# SCH_Party-Lights_2024-05-11.net
KiCad netlist of a schematic drawn in EasyEDA
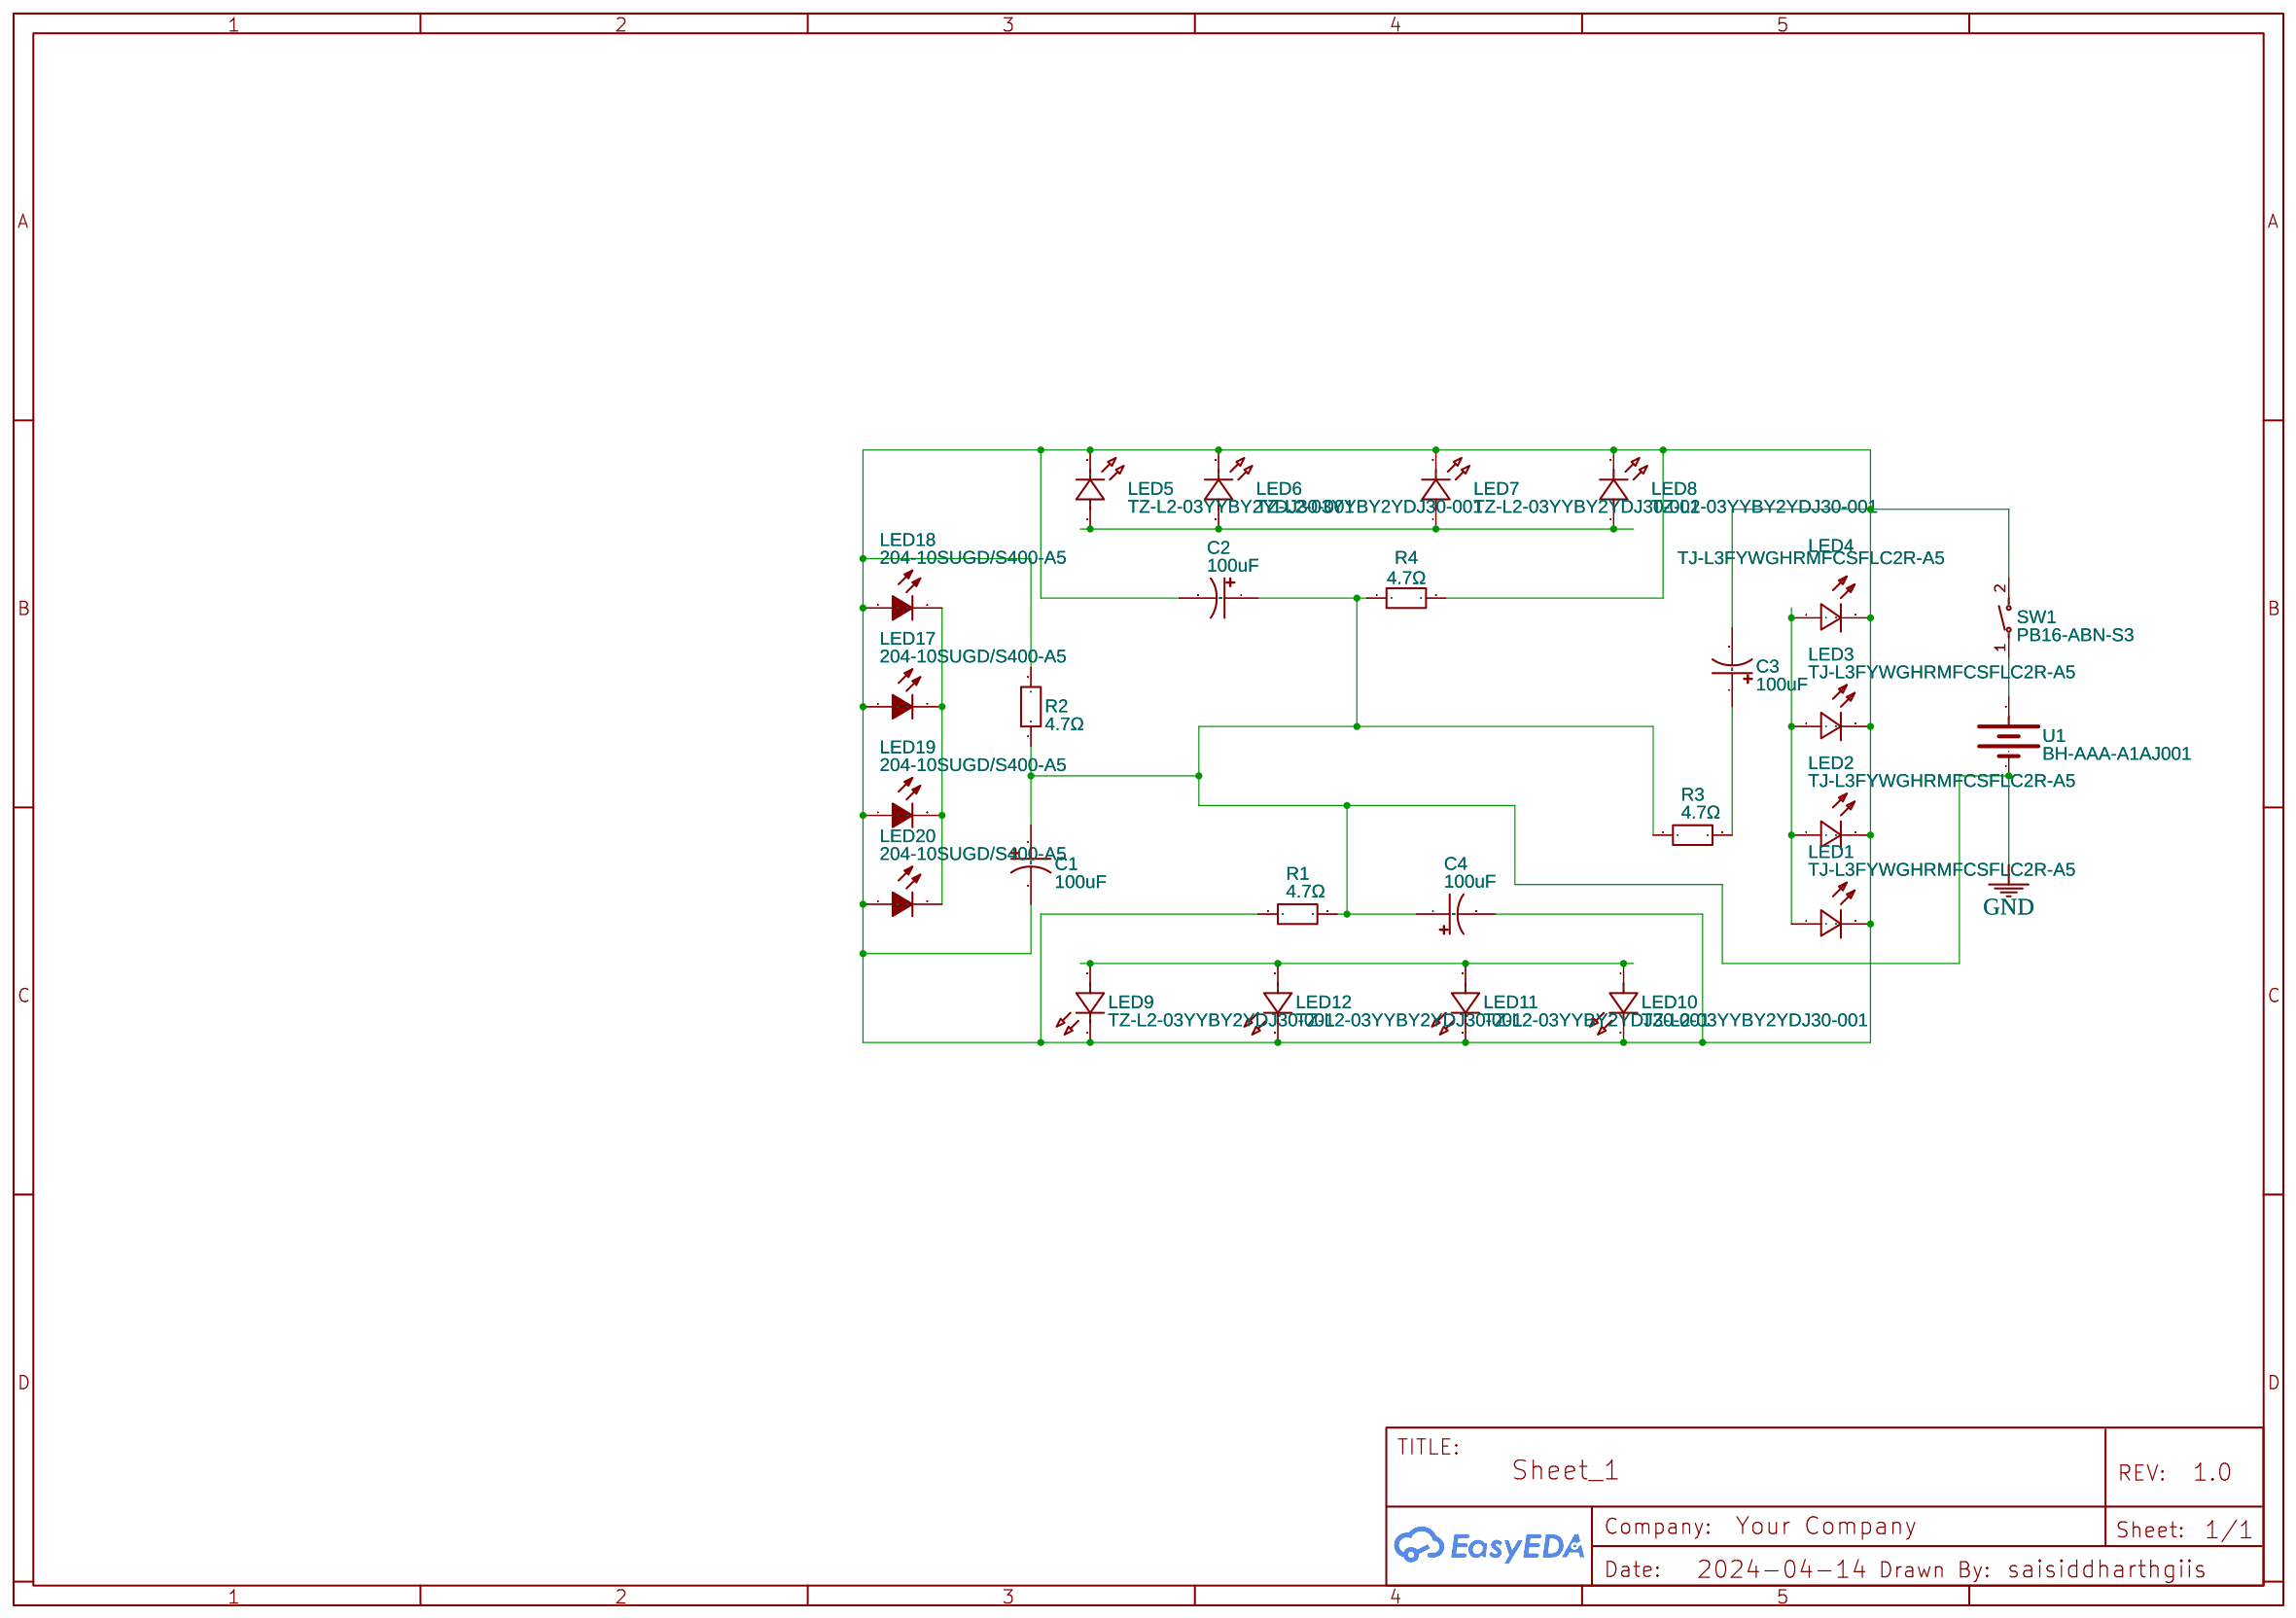
[diagram p0: schematic sheet]

(export (version "E")
  (design (tool "Eeschema 10.0.6"))
  (components
    (comp (ref "C1")
      (value "100uF")
      (fields
        (field (name "Manufacturer Part") "TLJA107M010R1400")
        (field (name "Manufacturer") "Kyocera AVX")
      )
      (libsource (lib "") (part "TLJA107M010R1400_2"))
    )
    (comp (ref "C2")
      (value "100uF")
      (fields
        (field (name "Manufacturer Part") "TLJA107M010R1400")
        (field (name "Manufacturer") "Kyocera AVX")
      )
      (libsource (lib "") (part "TLJA107M010R1400_1"))
    )
    (comp (ref "C3")
      (value "100uF")
      (fields
        (field (name "Manufacturer Part") "TLJA107M010R1400")
        (field (name "Manufacturer") "Kyocera AVX")
      )
      (libsource (lib "") (part "TLJA107M010R1400_3"))
    )
    (comp (ref "C4")
      (value "100uF")
      (fields
        (field (name "Manufacturer Part") "TLJA107M010R1400")
        (field (name "Manufacturer") "Kyocera AVX")
      )
      (libsource (lib "") (part "TLJA107M010R1400"))
    )
    (comp (ref "LED1")
      (value "TJ-L3FYWGHRMFCSFLC2R-A5")
      (fields (field (name "Manufacturer") "TOGIALED(统佳)"))
      (libsource (lib "") (part "TJ-L3FYWGHRMFCSFLC2R-A5"))
    )
    (comp (ref "LED2")
      (value "TJ-L3FYWGHRMFCSFLC2R-A5")
      (fields (field (name "Manufacturer") "TOGIALED(统佳)"))
      (libsource (lib "") (part "TJ-L3FYWGHRMFCSFLC2R-A5"))
    )
    (comp (ref "LED3")
      (value "TJ-L3FYWGHRMFCSFLC2R-A5")
      (fields (field (name "Manufacturer") "TOGIALED(统佳)"))
      (libsource (lib "") (part "TJ-L3FYWGHRMFCSFLC2R-A5"))
    )
    (comp (ref "LED4")
      (value "TJ-L3FYWGHRMFCSFLC2R-A5")
      (fields (field (name "Manufacturer") "TOGIALED(统佳)"))
      (libsource (lib "") (part "TJ-L3FYWGHRMFCSFLC2R-A5"))
    )
    (comp (ref "LED5")
      (value "TZ-L2-03YYBY2YDJ30-001")
      (fields (field (name "Manufacturer") "TUOZHAN(拓展光电)"))
      (libsource (lib "") (part "TZ-L2-03YYBY2YDJ30-001"))
    )
    (comp (ref "LED6")
      (value "TZ-L2-03YYBY2YDJ30-001")
      (fields (field (name "Manufacturer") "TUOZHAN(拓展光电)"))
      (libsource (lib "") (part "TZ-L2-03YYBY2YDJ30-001"))
    )
    (comp (ref "LED7")
      (value "TZ-L2-03YYBY2YDJ30-001")
      (fields (field (name "Manufacturer") "TUOZHAN(拓展光电)"))
      (libsource (lib "") (part "TZ-L2-03YYBY2YDJ30-001"))
    )
    (comp (ref "LED8")
      (value "TZ-L2-03YYBY2YDJ30-001")
      (fields (field (name "Manufacturer") "TUOZHAN(拓展光电)"))
      (libsource (lib "") (part "TZ-L2-03YYBY2YDJ30-001"))
    )
    (comp (ref "LED9")
      (value "TZ-L2-03YYBY2YDJ30-001")
      (fields (field (name "Manufacturer") "TUOZHAN(拓展光电)"))
      (libsource (lib "") (part "TZ-L2-03YYBY2YDJ30-001_1"))
    )
    (comp (ref "LED10")
      (value "TZ-L2-03YYBY2YDJ30-001")
      (fields (field (name "Manufacturer") "TUOZHAN(拓展光电)"))
      (libsource (lib "") (part "TZ-L2-03YYBY2YDJ30-001_1"))
    )
    (comp (ref "LED11")
      (value "TZ-L2-03YYBY2YDJ30-001")
      (fields (field (name "Manufacturer") "TUOZHAN(拓展光电)"))
      (libsource (lib "") (part "TZ-L2-03YYBY2YDJ30-001_1"))
    )
    (comp (ref "LED12")
      (value "TZ-L2-03YYBY2YDJ30-001")
      (fields (field (name "Manufacturer") "TUOZHAN(拓展光电)"))
      (libsource (lib "") (part "TZ-L2-03YYBY2YDJ30-001_1"))
    )
    (comp (ref "LED17")
      (value "204-10SUGD/S400-A5")
      (fields (field (name "Manufacturer") "EVERLIGHT(亿光)"))
      (libsource (lib "") (part "204-10SUGD/S400-A5"))
    )
    (comp (ref "LED18")
      (value "204-10SUGD/S400-A5")
      (fields (field (name "Manufacturer") "EVERLIGHT(亿光)"))
      (libsource (lib "") (part "204-10SUGD/S400-A5"))
    )
    (comp (ref "LED19")
      (value "204-10SUGD/S400-A5")
      (fields (field (name "Manufacturer") "EVERLIGHT(亿光)"))
      (libsource (lib "") (part "204-10SUGD/S400-A5"))
    )
    (comp (ref "LED20")
      (value "204-10SUGD/S400-A5")
      (fields (field (name "Manufacturer") "EVERLIGHT(亿光)"))
      (libsource (lib "") (part "204-10SUGD/S400-A5"))
    )
    (comp (ref "R1")
      (value "4.7Ω")
      (fields (field (name "Manufacturer Part") "AF0402FR-074R7L") (field (name "Manufacturer") "YAGEO(国巨)"))
      (libsource (lib "") (part "AF0402FR-074R7L_1"))
    )
    (comp (ref "R2")
      (value "4.7Ω")
      (fields (field (name "Manufacturer Part") "AF0402FR-074R7L") (field (name "Manufacturer") "YAGEO(国巨)"))
      (libsource (lib "") (part "AF0402FR-074R7L"))
    )
    (comp (ref "R3")
      (value "4.7Ω")
      (fields (field (name "Manufacturer Part") "AF0402FR-074R7L") (field (name "Manufacturer") "YAGEO(国巨)"))
      (libsource (lib "") (part "AF0402FR-074R7L_1"))
    )
    (comp (ref "R4")
      (value "4.7Ω")
      (fields (field (name "Manufacturer Part") "AF0402FR-074R7L") (field (name "Manufacturer") "YAGEO(国巨)"))
      (libsource (lib "") (part "AF0402FR-074R7L_1"))
    )
    (comp (ref "SW1")
      (value "PB16-ABN-S3")
      (fields (field (name "Manufacturer") "D-SWITCH(德崧)"))
      (libsource (lib "") (part "PB16-ABN-S3"))
    )
    (comp (ref "U1")
      (value "BH-AAA-A1AJ001")
      (fields (field (name "Manufacturer") "MYOUNG(美阳)"))
      (libsource (lib "") (part "BH-AAA-A1AJ001"))
    )
  )
  (nets
    (net (code "1") (name "GND") (class "Default")
      (node (ref "C1") (pin "1") (pinfunction "1_1") (pintype "unspecified"))
      (node (ref "C2") (pin "1") (pinfunction "1_1") (pintype "unspecified"))
      (node (ref "C4") (pin "1") (pinfunction "1_1") (pintype "unspecified"))
      (node (ref "R1") (pin "2") (pinfunction "2_2") (pintype "unspecified"))
      (node (ref "R2") (pin "1") (pinfunction "1_1") (pintype "unspecified"))
      (node (ref "R3") (pin "1") (pinfunction "1_1") (pintype "unspecified"))
      (node (ref "R4") (pin "1") (pinfunction "1_1") (pintype "unspecified"))
      (node (ref "U1") (pin "1") (pinfunction "-_1") (pintype "passive"))
    )
    (net (code "2") (name "Net-(C3-Pad1)") (class "Default")
      (node (ref "C3") (pin "1") (pinfunction "1_1") (pintype "unspecified"))
      (node (ref "R3") (pin "2") (pinfunction "2_2") (pintype "unspecified"))
    )
    (net (code "3") (name "Net-(LED1-Pad1)") (class "Default")
      (node (ref "LED1") (pin "1") (pinfunction "1_1") (pintype "unspecified"))
      (node (ref "LED2") (pin "1") (pinfunction "1_1") (pintype "unspecified"))
      (node (ref "LED3") (pin "1") (pinfunction "1_1") (pintype "unspecified"))
      (node (ref "LED4") (pin "1") (pinfunction "1_1") (pintype "unspecified"))
    )
    (net (code "4") (name "Net-(LED5-A)") (class "Default")
      (node (ref "LED5") (pin "1") (pinfunction "A_1") (pintype "unspecified"))
      (node (ref "LED6") (pin "1") (pinfunction "A_1") (pintype "unspecified"))
      (node (ref "LED7") (pin "1") (pinfunction "A_1") (pintype "unspecified"))
      (node (ref "LED8") (pin "1") (pinfunction "A_1") (pintype "unspecified"))
    )
    (net (code "5") (name "Net-(LED10-A)") (class "Default")
      (node (ref "LED10") (pin "1") (pinfunction "A_1") (pintype "unspecified"))
      (node (ref "LED11") (pin "1") (pinfunction "A_1") (pintype "unspecified"))
      (node (ref "LED12") (pin "1") (pinfunction "A_1") (pintype "unspecified"))
      (node (ref "LED9") (pin "1") (pinfunction "A_1") (pintype "unspecified"))
    )
    (net (code "6") (name "Net-(LED10-K)") (class "Default")
      (node (ref "C1") (pin "2") (pinfunction "2_2") (pintype "unspecified"))
      (node (ref "C2") (pin "2") (pinfunction "2_2") (pintype "unspecified"))
      (node (ref "C3") (pin "2") (pinfunction "2_2") (pintype "unspecified"))
      (node (ref "C4") (pin "2") (pinfunction "2_2") (pintype "unspecified"))
      (node (ref "LED1") (pin "2") (pinfunction "2_2") (pintype "unspecified"))
      (node (ref "LED10") (pin "2") (pinfunction "K_2") (pintype "unspecified"))
      (node (ref "LED11") (pin "2") (pinfunction "K_2") (pintype "unspecified"))
      (node (ref "LED12") (pin "2") (pinfunction "K_2") (pintype "unspecified"))
      (node (ref "LED17") (pin "1") (pinfunction "A_1") (pintype "input"))
      (node (ref "LED18") (pin "1") (pinfunction "A_1") (pintype "input"))
      (node (ref "LED19") (pin "1") (pinfunction "A_1") (pintype "input"))
      (node (ref "LED2") (pin "2") (pinfunction "2_2") (pintype "unspecified"))
      (node (ref "LED20") (pin "1") (pinfunction "A_1") (pintype "input"))
      (node (ref "LED3") (pin "2") (pinfunction "2_2") (pintype "unspecified"))
      (node (ref "LED4") (pin "2") (pinfunction "2_2") (pintype "unspecified"))
      (node (ref "LED5") (pin "2") (pinfunction "K_2") (pintype "unspecified"))
      (node (ref "LED6") (pin "2") (pinfunction "K_2") (pintype "unspecified"))
      (node (ref "LED7") (pin "2") (pinfunction "K_2") (pintype "unspecified"))
      (node (ref "LED8") (pin "2") (pinfunction "K_2") (pintype "unspecified"))
      (node (ref "LED9") (pin "2") (pinfunction "K_2") (pintype "unspecified"))
      (node (ref "R1") (pin "1") (pinfunction "1_1") (pintype "unspecified"))
      (node (ref "R2") (pin "2") (pinfunction "2_2") (pintype "unspecified"))
      (node (ref "R4") (pin "2") (pinfunction "2_2") (pintype "unspecified"))
      (node (ref "SW1") (pin "2") (pinfunction "2_2") (pintype "unspecified"))
    )
    (net (code "7") (name "Net-(LED17-K)") (class "Default")
      (node (ref "LED17") (pin "2") (pinfunction "K_2") (pintype "input"))
      (node (ref "LED18") (pin "2") (pinfunction "K_2") (pintype "input"))
      (node (ref "LED19") (pin "2") (pinfunction "K_2") (pintype "input"))
      (node (ref "LED20") (pin "2") (pinfunction "K_2") (pintype "input"))
    )
    (net (code "8") (name "Net-(U1-+)") (class "Default")
      (node (ref "SW1") (pin "1") (pinfunction "1_1") (pintype "unspecified"))
      (node (ref "U1") (pin "2") (pinfunction "+_2") (pintype "passive"))
    )
  )
)
